# Sam4S_Power_Distribution_5.net
KiCad netlist of a schematic drawn in Altium Designer
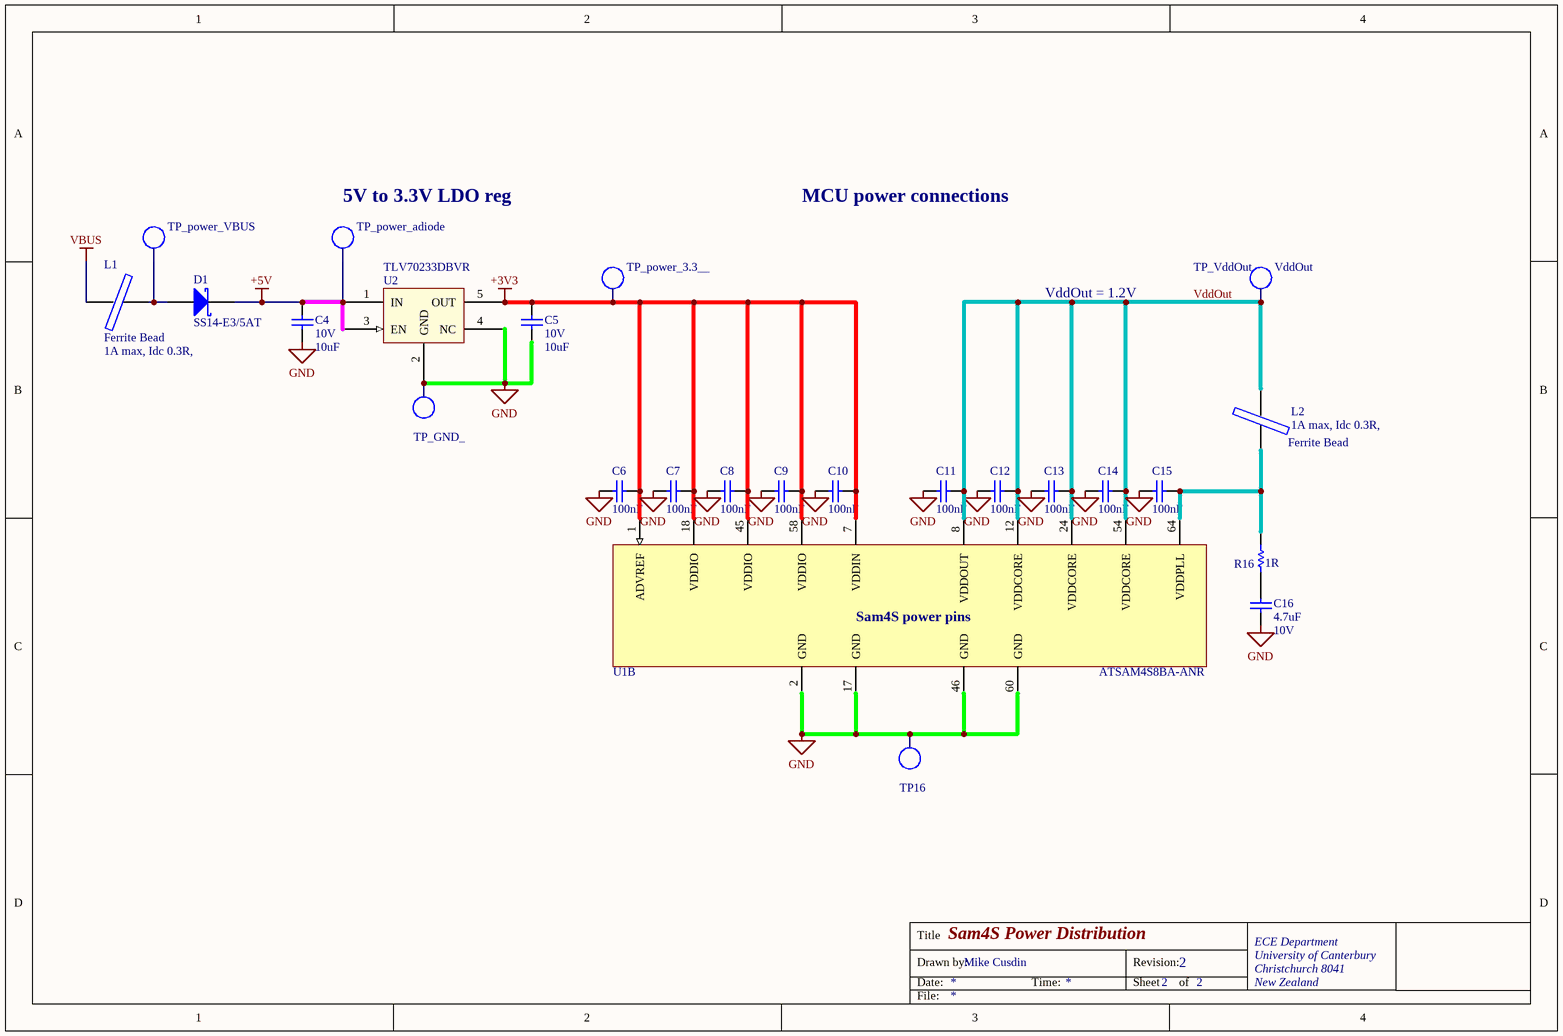
[diagram p0: Sam4S Power Distribution_5.SchDoc]

(export (version "E")
  (design (tool "Eeschema 10.0.6"))
  (components
    (comp (ref "C4")
      (value "10uF")
      (footprint "CAPC1608L")
      (description "CAP CER 10UF X5R +-20% 10V 0603")
      (fields (field (name "VOLTAGE - RATED") "10V"))
      (libsource (lib "ECE Components_15_8") (part "CC_10uF_0603"))
    )
    (comp (ref "C5")
      (value "10uF")
      (footprint "CAPC1608L")
      (description "CAP CER 10UF X5R +-20% 10V 0603")
      (fields (field (name "VOLTAGE - RATED") "10V"))
      (libsource (lib "ECE Components_15_8") (part "CC_10uF_0603"))
    )
    (comp (ref "C6")
      (value "100nF")
      (footprint "CAPC1608L")
      (description "CAP CER 100nF X7R +-10% 50V 0603")
      (libsource (lib "ECE Components_15_8") (part "CC_100nF_0603"))
    )
    (comp (ref "C7")
      (value "100nF")
      (footprint "CAPC1608L")
      (description "CAP CER 100nF X7R +-10% 50V 0603")
      (libsource (lib "ECE Components_15_8") (part "CC_100nF_0603"))
    )
    (comp (ref "C8")
      (value "100nF")
      (footprint "CAPC1608L")
      (description "CAP CER 100nF X7R +-10% 50V 0603")
      (libsource (lib "ECE Components_15_8") (part "CC_100nF_0603"))
    )
    (comp (ref "C9")
      (value "100nF")
      (footprint "CAPC1608L")
      (description "CAP CER 100nF X7R +-10% 50V 0603")
      (libsource (lib "ECE Components_15_8") (part "CC_100nF_0603"))
    )
    (comp (ref "C10")
      (value "100nF")
      (footprint "CAPC1608L")
      (description "CAP CER 100nF X7R +-10% 50V 0603")
      (libsource (lib "ECE Components_15_8") (part "CC_100nF_0603"))
    )
    (comp (ref "C11")
      (value "100nF")
      (footprint "CAPC1608L")
      (description "CAP CER 100nF X7R +-10% 50V 0603")
      (libsource (lib "ECE Components_15_8") (part "CC_100nF_0603"))
    )
    (comp (ref "C12")
      (value "100nF")
      (footprint "CAPC1608L")
      (description "CAP CER 100nF X7R +-10% 50V 0603")
      (libsource (lib "ECE Components_15_8") (part "CC_100nF_0603"))
    )
    (comp (ref "C13")
      (value "100nF")
      (footprint "CAPC1608L")
      (description "CAP CER 100nF X7R +-10% 50V 0603")
      (libsource (lib "ECE Components_15_8") (part "CC_100nF_0603"))
    )
    (comp (ref "C14")
      (value "100nF")
      (footprint "CAPC1608L")
      (description "CAP CER 100nF X7R +-10% 50V 0603")
      (libsource (lib "ECE Components_15_8") (part "CC_100nF_0603"))
    )
    (comp (ref "C15")
      (value "100nF")
      (footprint "CAPC1608L")
      (description "CAP CER 100nF X7R +-10% 50V 0603")
      (libsource (lib "ECE Components_15_8") (part "CC_100nF_0603"))
    )
    (comp (ref "C16")
      (value "4.7uF")
      (footprint "CAPC1608N")
      (description "CAP CER 4.7uF X5R +-20%  10V 0603")
      (fields (field (name "MAX VOLTAGE") "10V"))
      (libsource (lib "ECE Components_15_8") (part "CC_4.7uF_0603"))
    )
    (comp (ref "D1")
      (value "SS14-E3/5AT")
      (footprint "DIOM4227X23N")
      (description "DIODE, SCHOTTKY, 1A, 40V, DO-214AC")
      (fields
        (field (name "MANUFACTURER") "VISHAY GENERAL SEMICONDUCTOR")
        (field (name "MANUFACTURER PART NUMBER") "SS14-E3/5AT")
      )
      (libsource (lib "ECE Components_15_8") (part "DS_SS14E3"))
    )
    (comp (ref "L1")
      (value "Ferrite Bead")
      (footprint "INDC3216L")
      (description "Ferrite Bead, Rdc 0.3R, Z100MHZ 600R, Imax 1A, SMD 1206")
      (fields
        (field (name "MANUFACTURER") "FAIR-RITE")
        (field (name "MANUFACTURER PART NUMBER") "2512066017Y1")
        (field (name "ALTIUM_VALUE") "1A max, Idc 0.3R,")
      )
      (libsource (lib "ECE Components_15_8") (part "IN_Ferrite-Bead"))
    )
    (comp (ref "L2")
      (value "Ferrite Bead")
      (footprint "INDC3216L")
      (description "Ferrite Bead, Rdc 0.3R, Z100MHZ 600R, Imax 1A, SMD 1206")
      (fields
        (field (name "MANUFACTURER") "FAIR-RITE")
        (field (name "MANUFACTURER PART NUMBER") "2512066017Y1")
        (field (name "ALTIUM_VALUE") "1A max, Idc 0.3R,")
      )
      (libsource (lib "ECE Components_15_8") (part "IN_Ferrite-Bead"))
    )
    (comp (ref "R16")
      (value "1R")
      (footprint "RESC3216L")
      (description "RES 1R OHM 1/4W 5% 1206 SMD")
      (libsource (lib "ECE Components_15_8") (part "RT_1R"))
    )
    (comp (ref "TP16")
      (value "Gnd")
      (footprint "TP_0805")
      (description "Test Point 2.0X0.9X1.2mm SMD")
      (fields
        (field (name "MANUFACTURER") "TE Connectivity AMP Connectors")
        (field (name "MANUFACTURER PART NUMBER") "1625854-2")
      )
      (libsource (lib "ECE Components_15_8") (part "TP_0805"))
    )
    (comp (ref "TP_GND_")
      (value "Gnd")
      (footprint "TP_0805")
      (description "Test Point 2.0X0.9X1.2mm SMD")
      (fields
        (field (name "MANUFACTURER") "TE Connectivity AMP Connectors")
        (field (name "MANUFACTURER PART NUMBER") "1625854-2")
      )
      (libsource (lib "ECE Components_15_8") (part "TP_0805"))
    )
    (comp (ref "TP_power_3.3__")
      (value "3V3")
      (footprint "TP_0805")
      (description "Test Point 2.0X0.9X1.2mm SMD")
      (fields
        (field (name "MANUFACTURER") "TE Connectivity AMP Connectors")
        (field (name "MANUFACTURER PART NUMBER") "1625854-2")
      )
      (libsource (lib "ECE Components_15_8") (part "TP_0805"))
    )
    (comp (ref "TP_power_adiode")
      (value "3V3")
      (footprint "TP_0805")
      (description "Test Point 2.0X0.9X1.2mm SMD")
      (fields
        (field (name "MANUFACTURER") "TE Connectivity AMP Connectors")
        (field (name "MANUFACTURER PART NUMBER") "1625854-2")
      )
      (libsource (lib "ECE Components_15_8") (part "TP_0805"))
    )
    (comp (ref "TP_power_VBUS")
      (value "3V3")
      (footprint "TP_0805")
      (description "Test Point 2.0X0.9X1.2mm SMD")
      (fields
        (field (name "MANUFACTURER") "TE Connectivity AMP Connectors")
        (field (name "MANUFACTURER PART NUMBER") "1625854-2")
      )
      (libsource (lib "ECE Components_15_8") (part "TP_0805"))
    )
    (comp (ref "TP_VddOut")
      (value "VddOut")
      (footprint "TP_0805")
      (description "Test Point 2.0X0.9X1.2mm SMD")
      (fields
        (field (name "MANUFACTURER") "TE Connectivity AMP Connectors")
        (field (name "MANUFACTURER PART NUMBER") "1625854-2")
      )
      (libsource (lib "ECE Components_15_8") (part "TP_0805"))
    )
    (comp (ref "U1")
      (value "ATSAM4S8BA-ANR")
      (footprint "LQFP64_L")
      (description "IC MCU 32BIT 512KB FLASH 64LQFP")
      (fields (field (name "MANUFACTURER") "Atmel"))
      (libsource (lib "ECE Components_15_8") (part "SE_ATSAM4S16BA-MU"))
    )
    (comp (ref "U2")
      (value "TLV70233DBVR")
      (footprint "SOT95P280X145-5N")
      (description "IC REG LDO 3.3V 0.3A SOT23-5")
      (fields
        (field (name "MANUFACTURER") "Texas Instruments")
        (field (name "MANUFACTURER PART NUMBER") "TLV70233DBVR")
      )
      (libsource (lib "ECE Components_15_8") (part "SV_TLV70233DBVR"))
    )
  )
  (nets
    (net (code "1") (name "+3V3") (class "Default")
      (node (ref "C10") (pin "2") (pinfunction "2_2") (pintype "passive"))
      (node (ref "C5") (pin "1") (pinfunction "1_1") (pintype "passive"))
      (node (ref "C6") (pin "2") (pinfunction "2_2") (pintype "passive"))
      (node (ref "C7") (pin "2") (pinfunction "2_2") (pintype "passive"))
      (node (ref "C8") (pin "2") (pinfunction "2_2") (pintype "passive"))
      (node (ref "C9") (pin "2") (pinfunction "2_2") (pintype "passive"))
      (node (ref "TP_power_3.3__") (pin "1") (pinfunction "TP_1") (pintype "passive"))
      (node (ref "U1") (pin "1") (pinfunction "ADVREF_1") (pintype "input"))
      (node (ref "U1") (pin "18") (pinfunction "VDDIO_18") (pintype "power_in"))
      (node (ref "U1") (pin "45") (pinfunction "VDDIO_45") (pintype "power_in"))
      (node (ref "U1") (pin "58") (pinfunction "VDDIO_58") (pintype "power_in"))
      (node (ref "U1") (pin "7") (pinfunction "VDDIN_7") (pintype "power_in"))
      (node (ref "U2") (pin "5") (pinfunction "OUT_5") (pintype "power_in"))
    )
    (net (code "2") (name "+5V") (class "Default")
      (node (ref "C4") (pin "1") (pinfunction "1_1") (pintype "passive"))
      (node (ref "D1") (pin "1") (pinfunction "K_1") (pintype "passive"))
      (node (ref "TP_power_adiode") (pin "1") (pinfunction "TP_1") (pintype "passive"))
      (node (ref "U2") (pin "1") (pinfunction "IN_1") (pintype "power_in"))
      (node (ref "U2") (pin "3") (pinfunction "EN_3") (pintype "input"))
    )
    (net (code "3") (name "/VddOut") (class "Default")
      (node (ref "C11") (pin "2") (pinfunction "2_2") (pintype "passive"))
      (node (ref "C12") (pin "2") (pinfunction "2_2") (pintype "passive"))
      (node (ref "C13") (pin "2") (pinfunction "2_2") (pintype "passive"))
      (node (ref "C14") (pin "2") (pinfunction "2_2") (pintype "passive"))
      (node (ref "L2") (pin "2") (pinfunction "2_2") (pintype "passive"))
      (node (ref "TP_VddOut") (pin "1") (pinfunction "TP_1") (pintype "passive"))
      (node (ref "U1") (pin "12") (pinfunction "VDDCORE_12") (pintype "power_in"))
      (node (ref "U1") (pin "24") (pinfunction "VDDCORE_24") (pintype "power_in"))
      (node (ref "U1") (pin "54") (pinfunction "VDDCORE_54") (pintype "power_in"))
      (node (ref "U1") (pin "8") (pinfunction "VDDOUT_8") (pintype "power_in"))
    )
    (net (code "4") (name "GND") (class "Default")
      (node (ref "C10") (pin "1") (pinfunction "1_1") (pintype "passive"))
      (node (ref "C11") (pin "1") (pinfunction "1_1") (pintype "passive"))
      (node (ref "C12") (pin "1") (pinfunction "1_1") (pintype "passive"))
      (node (ref "C13") (pin "1") (pinfunction "1_1") (pintype "passive"))
      (node (ref "C14") (pin "1") (pinfunction "1_1") (pintype "passive"))
      (node (ref "C15") (pin "1") (pinfunction "1_1") (pintype "passive"))
      (node (ref "C16") (pin "1") (pinfunction "1_1") (pintype "passive"))
      (node (ref "C4") (pin "2") (pinfunction "2_2") (pintype "passive"))
      (node (ref "C5") (pin "2") (pinfunction "2_2") (pintype "passive"))
      (node (ref "C6") (pin "1") (pinfunction "1_1") (pintype "passive"))
      (node (ref "C7") (pin "1") (pinfunction "1_1") (pintype "passive"))
      (node (ref "C8") (pin "1") (pinfunction "1_1") (pintype "passive"))
      (node (ref "C9") (pin "1") (pinfunction "1_1") (pintype "passive"))
      (node (ref "TP16") (pin "1") (pinfunction "TP_1") (pintype "passive"))
      (node (ref "TP_GND_") (pin "1") (pinfunction "TP_1") (pintype "passive"))
      (node (ref "U1") (pin "17") (pinfunction "GND_17") (pintype "power_in"))
      (node (ref "U1") (pin "2") (pinfunction "GND_2") (pintype "power_in"))
      (node (ref "U1") (pin "46") (pinfunction "GND_46") (pintype "power_in"))
      (node (ref "U1") (pin "60") (pinfunction "GND_60") (pintype "power_in"))
      (node (ref "U2") (pin "2") (pinfunction "GND_2") (pintype "power_in"))
      (node (ref "U2") (pin "4") (pinfunction "NC_4") (pintype "passive"))
    )
    (net (code "5") (name "Net-(C16-Pad2)") (class "Default")
      (node (ref "C16") (pin "2") (pinfunction "2_2") (pintype "passive"))
      (node (ref "R16") (pin "1") (pinfunction "1_1") (pintype "passive"))
    )
    (net (code "6") (name "Net-(D1-A)") (class "Default")
      (node (ref "D1") (pin "2") (pinfunction "A_2") (pintype "passive"))
      (node (ref "L1") (pin "1") (pinfunction "1_1") (pintype "passive"))
      (node (ref "TP_power_VBUS") (pin "1") (pinfunction "TP_1") (pintype "passive"))
    )
    (net (code "7") (name "Net-(U1B-VDDPLL)") (class "Default")
      (node (ref "C15") (pin "2") (pinfunction "2_2") (pintype "passive"))
      (node (ref "L2") (pin "1") (pinfunction "1_1") (pintype "passive"))
      (node (ref "R16") (pin "2") (pinfunction "2_2") (pintype "passive"))
      (node (ref "U1") (pin "64") (pinfunction "VDDPLL_64") (pintype "power_in"))
    )
    (net (code "8") (name "VBUS") (class "Default")
      (node (ref "L1") (pin "2") (pinfunction "2_2") (pintype "passive"))
    )
  )
)
